# HAE_MCU.net
KiCad netlist of a schematic drawn in Altium Designer
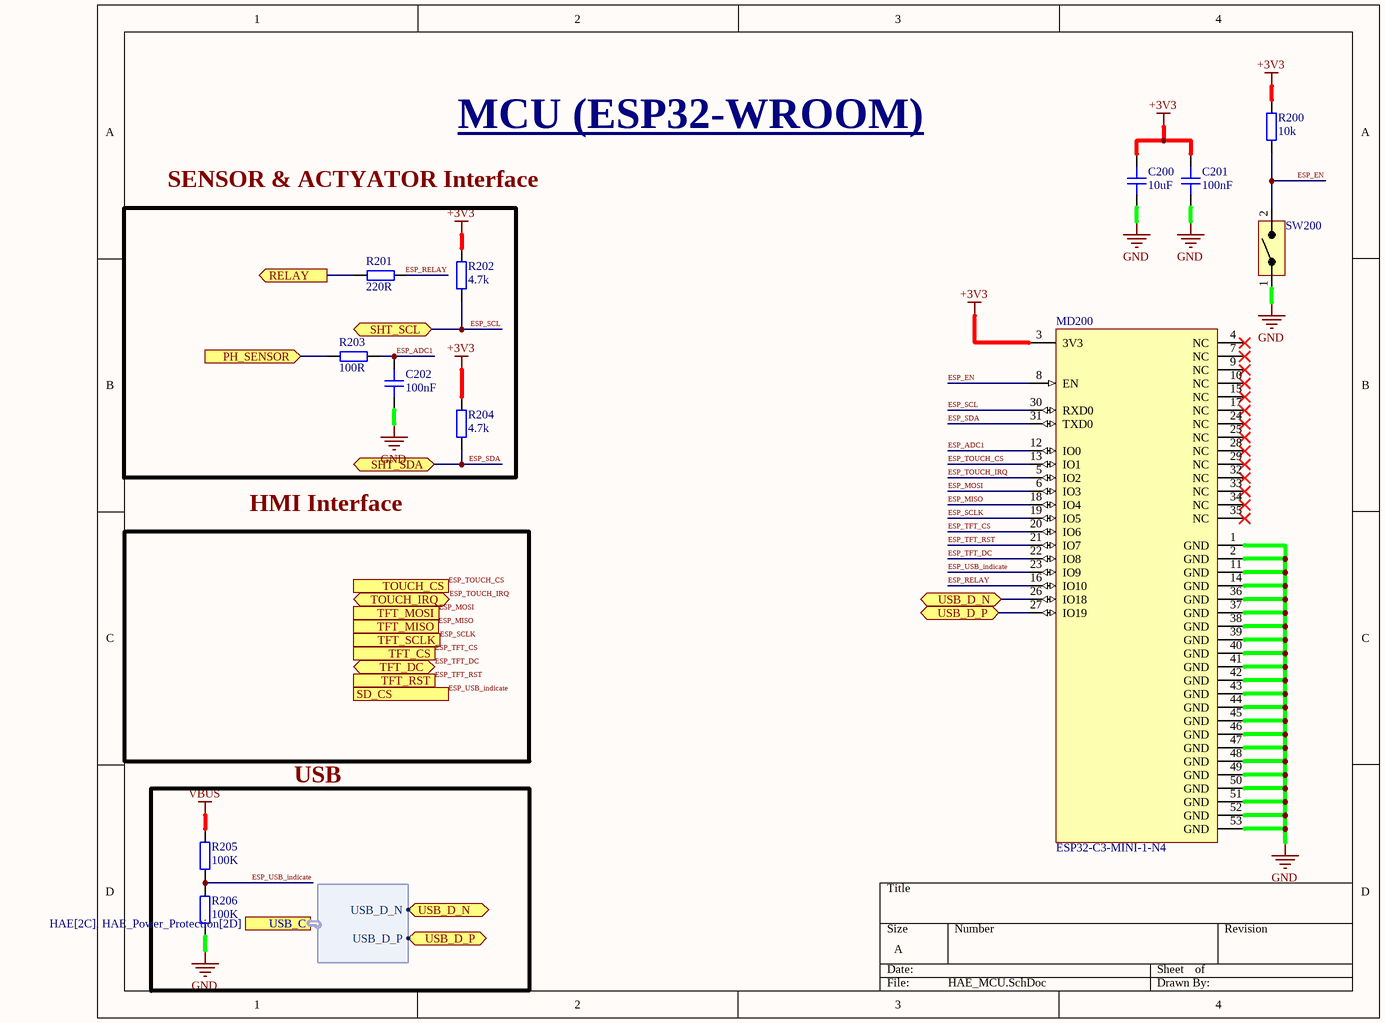
[diagram p0: HAE_MCU.SchDoc]

(export (version "E")
  (design (tool "Eeschema 10.0.6"))
  (components
    (comp (ref "C200")
      (value "10uF")
      (footprint "CAP_0402")
      (description "Capacitor SMD 0402")
      (libsource (lib "PhilsLab_Library") (part "CAP_0402"))
    )
    (comp (ref "C201")
      (value "100nF")
      (footprint "CAP_0603")
      (description "Capacitor SMD 0603")
      (libsource (lib "PhilsLab_Library") (part "CAP_0603"))
    )
    (comp (ref "C202")
      (value "100nF")
      (footprint "CAP_0603")
      (description "Capacitor SMD 0603")
      (libsource (lib "PhilsLab_Library") (part "CAP_0603"))
    )
    (comp (ref "MD200")
      (value "ESP32-C3-MINI-1-N4")
      (footprint "FP-ESP32-C3-MINI-1-N4-MFG")
      (description "Multiprotocol Modules SMD module, ESP32-C3FN4, PCB antenna, -40 C +85 C")
      (libsource (lib "Altium Content Vault") (part "ESP32-C3-MINI-1-N4"))
    )
    (comp (ref "R200")
      (value "10k")
      (footprint "RES_0402")
      (description "Resistor SMD 0402")
      (libsource (lib "PhilsLab_Library") (part "RES_0402"))
    )
    (comp (ref "R201")
      (value "220R")
      (footprint "RES_0402")
      (description "Resistor SMD 0402")
      (libsource (lib "PhilsLab_Library") (part "RES_0402"))
    )
    (comp (ref "R202")
      (value "4.7k")
      (footprint "RES_0402")
      (description "Resistor SMD 0402")
      (libsource (lib "PhilsLab_Library") (part "RES_0402"))
    )
    (comp (ref "R203")
      (value "100R")
      (footprint "RES_0402")
      (description "Resistor SMD 0402")
      (libsource (lib "PhilsLab_Library") (part "RES_0402"))
    )
    (comp (ref "R204")
      (value "4.7k")
      (footprint "RES_0402")
      (description "Resistor SMD 0402")
      (libsource (lib "PhilsLab_Library") (part "RES_0402"))
    )
    (comp (ref "R205")
      (value "100K")
      (footprint "RES_0402")
      (description "Resistor SMD 0402")
      (libsource (lib "PhilsLab_Library") (part "RES_0402"))
    )
    (comp (ref "R206")
      (value "100K")
      (footprint "RES_0402")
      (description "Resistor SMD 0402")
      (libsource (lib "PhilsLab_Library") (part "RES_0402"))
    )
    (comp (ref "SW200")
      (value "B3U-1000P")
      (footprint "B3U_1000P")
      (description "Tactile Switch SPST-NO Top Actuated Surface Mount")
      (fields (field (name "MANUFACTURER") "Omron"))
      (libsource (lib "OU-iVCCS") (part "B3U-1000P"))
    )
  )
  (nets
    (net (code "2") (name "+3V3") (class "Default")
      (node (ref "C200") (pin "2") (pinfunction "2_2") (pintype "passive"))
      (node (ref "C201") (pin "2") (pinfunction "2_2") (pintype "passive"))
      (node (ref "MD200") (pin "3") (pinfunction "3V3_3") (pintype "power_in"))
      (node (ref "R200") (pin "2") (pinfunction "2_2") (pintype "passive"))
      (node (ref "R202") (pin "2") (pinfunction "2_2") (pintype "passive"))
      (node (ref "R204") (pin "2") (pinfunction "2_2") (pintype "passive"))
    )
    (net (code "3") (name "/ESP_ADC1") (class "Default")
      (node (ref "C202") (pin "2") (pinfunction "2_2") (pintype "passive"))
      (node (ref "MD200") (pin "12") (pinfunction "IO0_12") (pintype "bidirectional"))
      (node (ref "R203") (pin "1") (pinfunction "1_1") (pintype "passive"))
    )
    (net (code "4") (name "/ESP_EN") (class "Default")
      (node (ref "MD200") (pin "8") (pinfunction "EN_8") (pintype "input"))
      (node (ref "R200") (pin "1") (pinfunction "1_1") (pintype "passive"))
      (node (ref "SW200") (pin "2") (pintype "passive"))
    )
    (net (code "5") (name "/ESP_MISO") (class "Default")
      (node (ref "MD200") (pin "18") (pinfunction "IO4_18") (pintype "bidirectional"))
    )
    (net (code "6") (name "/ESP_MOSI") (class "Default")
      (node (ref "MD200") (pin "6") (pinfunction "IO3_6") (pintype "bidirectional"))
    )
    (net (code "7") (name "/ESP_RELAY") (class "Default")
      (node (ref "MD200") (pin "16") (pinfunction "IO10_16") (pintype "bidirectional"))
      (node (ref "R201") (pin "1") (pinfunction "1_1") (pintype "passive"))
    )
    (net (code "8") (name "/ESP_SCL") (class "Default")
      (node (ref "MD200") (pin "30") (pinfunction "RXD0_30") (pintype "bidirectional"))
      (node (ref "R202") (pin "1") (pinfunction "1_1") (pintype "passive"))
    )
    (net (code "9") (name "/ESP_SCLK") (class "Default")
      (node (ref "MD200") (pin "19") (pinfunction "IO5_19") (pintype "bidirectional"))
    )
    (net (code "10") (name "/ESP_SDA") (class "Default")
      (node (ref "MD200") (pin "31") (pinfunction "TXD0_31") (pintype "bidirectional"))
      (node (ref "R204") (pin "1") (pinfunction "1_1") (pintype "passive"))
    )
    (net (code "11") (name "/ESP_TFT_CS") (class "Default")
      (node (ref "MD200") (pin "20") (pinfunction "IO6_20") (pintype "bidirectional"))
    )
    (net (code "12") (name "/ESP_TFT_DC") (class "Default")
      (node (ref "MD200") (pin "22") (pinfunction "IO8_22") (pintype "bidirectional"))
    )
    (net (code "13") (name "/ESP_TFT_RST") (class "Default")
      (node (ref "MD200") (pin "21") (pinfunction "IO7_21") (pintype "bidirectional"))
    )
    (net (code "14") (name "/ESP_TOUCH_CS") (class "Default")
      (node (ref "MD200") (pin "13") (pinfunction "IO1_13") (pintype "bidirectional"))
    )
    (net (code "15") (name "/ESP_TOUCH_IRQ") (class "Default")
      (node (ref "MD200") (pin "5") (pinfunction "IO2_5") (pintype "bidirectional"))
    )
    (net (code "16") (name "/ESP_USB_indicate") (class "Default")
      (node (ref "MD200") (pin "23") (pinfunction "IO9_23") (pintype "bidirectional"))
      (node (ref "R205") (pin "2") (pinfunction "2_2") (pintype "passive"))
      (node (ref "R206") (pin "1") (pinfunction "1_1") (pintype "passive"))
    )
    (net (code "17") (name "/PH_SENSOR") (class "Default")
      (node (ref "R203") (pin "2") (pinfunction "2_2") (pintype "passive"))
    )
    (net (code "18") (name "/RELAY") (class "Default")
      (node (ref "R201") (pin "2") (pinfunction "2_2") (pintype "passive"))
    )
    (net (code "19") (name "/USB_D_N") (class "Default")
      (node (ref "MD200") (pin "26") (pinfunction "IO18_26") (pintype "bidirectional"))
    )
    (net (code "20") (name "/USB_D_P") (class "Default")
      (node (ref "MD200") (pin "27") (pinfunction "IO19_27") (pintype "bidirectional"))
    )
    (net (code "22") (name "GND") (class "Default")
      (node (ref "C200") (pin "1") (pinfunction "1_1") (pintype "passive"))
      (node (ref "C201") (pin "1") (pinfunction "1_1") (pintype "passive"))
      (node (ref "C202") (pin "1") (pinfunction "1_1") (pintype "passive"))
      (node (ref "MD200") (pin "1") (pinfunction "GND_1") (pintype "power_in"))
      (node (ref "MD200") (pin "11") (pinfunction "GND_11") (pintype "power_in"))
      (node (ref "MD200") (pin "14") (pinfunction "GND_14") (pintype "power_in"))
      (node (ref "MD200") (pin "2") (pinfunction "GND_2") (pintype "power_in"))
      (node (ref "MD200") (pin "36") (pinfunction "GND_36") (pintype "power_in"))
      (node (ref "MD200") (pin "37") (pinfunction "GND_37") (pintype "power_in"))
      (node (ref "MD200") (pin "38") (pinfunction "GND_38") (pintype "power_in"))
      (node (ref "MD200") (pin "39") (pinfunction "GND_39") (pintype "power_in"))
      (node (ref "MD200") (pin "40") (pinfunction "GND_40") (pintype "power_in"))
      (node (ref "MD200") (pin "41") (pinfunction "GND_41") (pintype "power_in"))
      (node (ref "MD200") (pin "42") (pinfunction "GND_42") (pintype "power_in"))
      (node (ref "MD200") (pin "43") (pinfunction "GND_43") (pintype "power_in"))
      (node (ref "MD200") (pin "44") (pinfunction "GND_44") (pintype "power_in"))
      (node (ref "MD200") (pin "45") (pinfunction "GND_45") (pintype "power_in"))
      (node (ref "MD200") (pin "46") (pinfunction "GND_46") (pintype "power_in"))
      (node (ref "MD200") (pin "47") (pinfunction "GND_47") (pintype "power_in"))
      (node (ref "MD200") (pin "48") (pinfunction "GND_48") (pintype "power_in"))
      (node (ref "MD200") (pin "49") (pinfunction "GND_49") (pintype "power_in"))
      (node (ref "MD200") (pin "50") (pinfunction "GND_50") (pintype "power_in"))
      (node (ref "MD200") (pin "51") (pinfunction "GND_51") (pintype "power_in"))
      (node (ref "MD200") (pin "52") (pinfunction "GND_52") (pintype "power_in"))
      (node (ref "MD200") (pin "53") (pinfunction "GND_53") (pintype "power_in"))
      (node (ref "R206") (pin "2") (pinfunction "2_2") (pintype "passive"))
      (node (ref "SW200") (pin "1") (pintype "passive"))
    )
    (net (code "23") (name "VBUS") (class "Default")
      (node (ref "R205") (pin "1") (pinfunction "1_1") (pintype "passive"))
    )
    (net (code "24") (name "unconnected-(MD200-NC-Pad4)") (class "Default")
      (node (ref "MD200") (pin "4") (pinfunction "NC_4") (pintype "passive+no_connect"))
    )
    (net (code "25") (name "unconnected-(MD200-NC-Pad7)") (class "Default")
      (node (ref "MD200") (pin "7") (pinfunction "NC_7") (pintype "passive+no_connect"))
    )
    (net (code "26") (name "unconnected-(MD200-NC-Pad9)") (class "Default")
      (node (ref "MD200") (pin "9") (pinfunction "NC_9") (pintype "passive+no_connect"))
    )
    (net (code "27") (name "unconnected-(MD200-NC-Pad10)") (class "Default")
      (node (ref "MD200") (pin "10") (pinfunction "NC_10") (pintype "passive+no_connect"))
    )
    (net (code "28") (name "unconnected-(MD200-NC-Pad15)") (class "Default")
      (node (ref "MD200") (pin "15") (pinfunction "NC_15") (pintype "passive+no_connect"))
    )
    (net (code "29") (name "unconnected-(MD200-NC-Pad17)") (class "Default")
      (node (ref "MD200") (pin "17") (pinfunction "NC_17") (pintype "passive+no_connect"))
    )
    (net (code "30") (name "unconnected-(MD200-NC-Pad24)") (class "Default")
      (node (ref "MD200") (pin "24") (pinfunction "NC_24") (pintype "passive+no_connect"))
    )
    (net (code "31") (name "unconnected-(MD200-NC-Pad25)") (class "Default")
      (node (ref "MD200") (pin "25") (pinfunction "NC_25") (pintype "passive+no_connect"))
    )
    (net (code "32") (name "unconnected-(MD200-NC-Pad28)") (class "Default")
      (node (ref "MD200") (pin "28") (pinfunction "NC_28") (pintype "passive+no_connect"))
    )
    (net (code "33") (name "unconnected-(MD200-NC-Pad29)") (class "Default")
      (node (ref "MD200") (pin "29") (pinfunction "NC_29") (pintype "passive+no_connect"))
    )
    (net (code "34") (name "unconnected-(MD200-NC-Pad32)") (class "Default")
      (node (ref "MD200") (pin "32") (pinfunction "NC_32") (pintype "passive+no_connect"))
    )
    (net (code "35") (name "unconnected-(MD200-NC-Pad33)") (class "Default")
      (node (ref "MD200") (pin "33") (pinfunction "NC_33") (pintype "passive+no_connect"))
    )
    (net (code "36") (name "unconnected-(MD200-NC-Pad34)") (class "Default")
      (node (ref "MD200") (pin "34") (pinfunction "NC_34") (pintype "passive+no_connect"))
    )
    (net (code "37") (name "unconnected-(MD200-NC-Pad35)") (class "Default")
      (node (ref "MD200") (pin "35") (pinfunction "NC_35") (pintype "passive+no_connect"))
    )
  )
)
